# 02_PMIC_POWER.net
KiCad netlist of a schematic drawn in Altium Designer
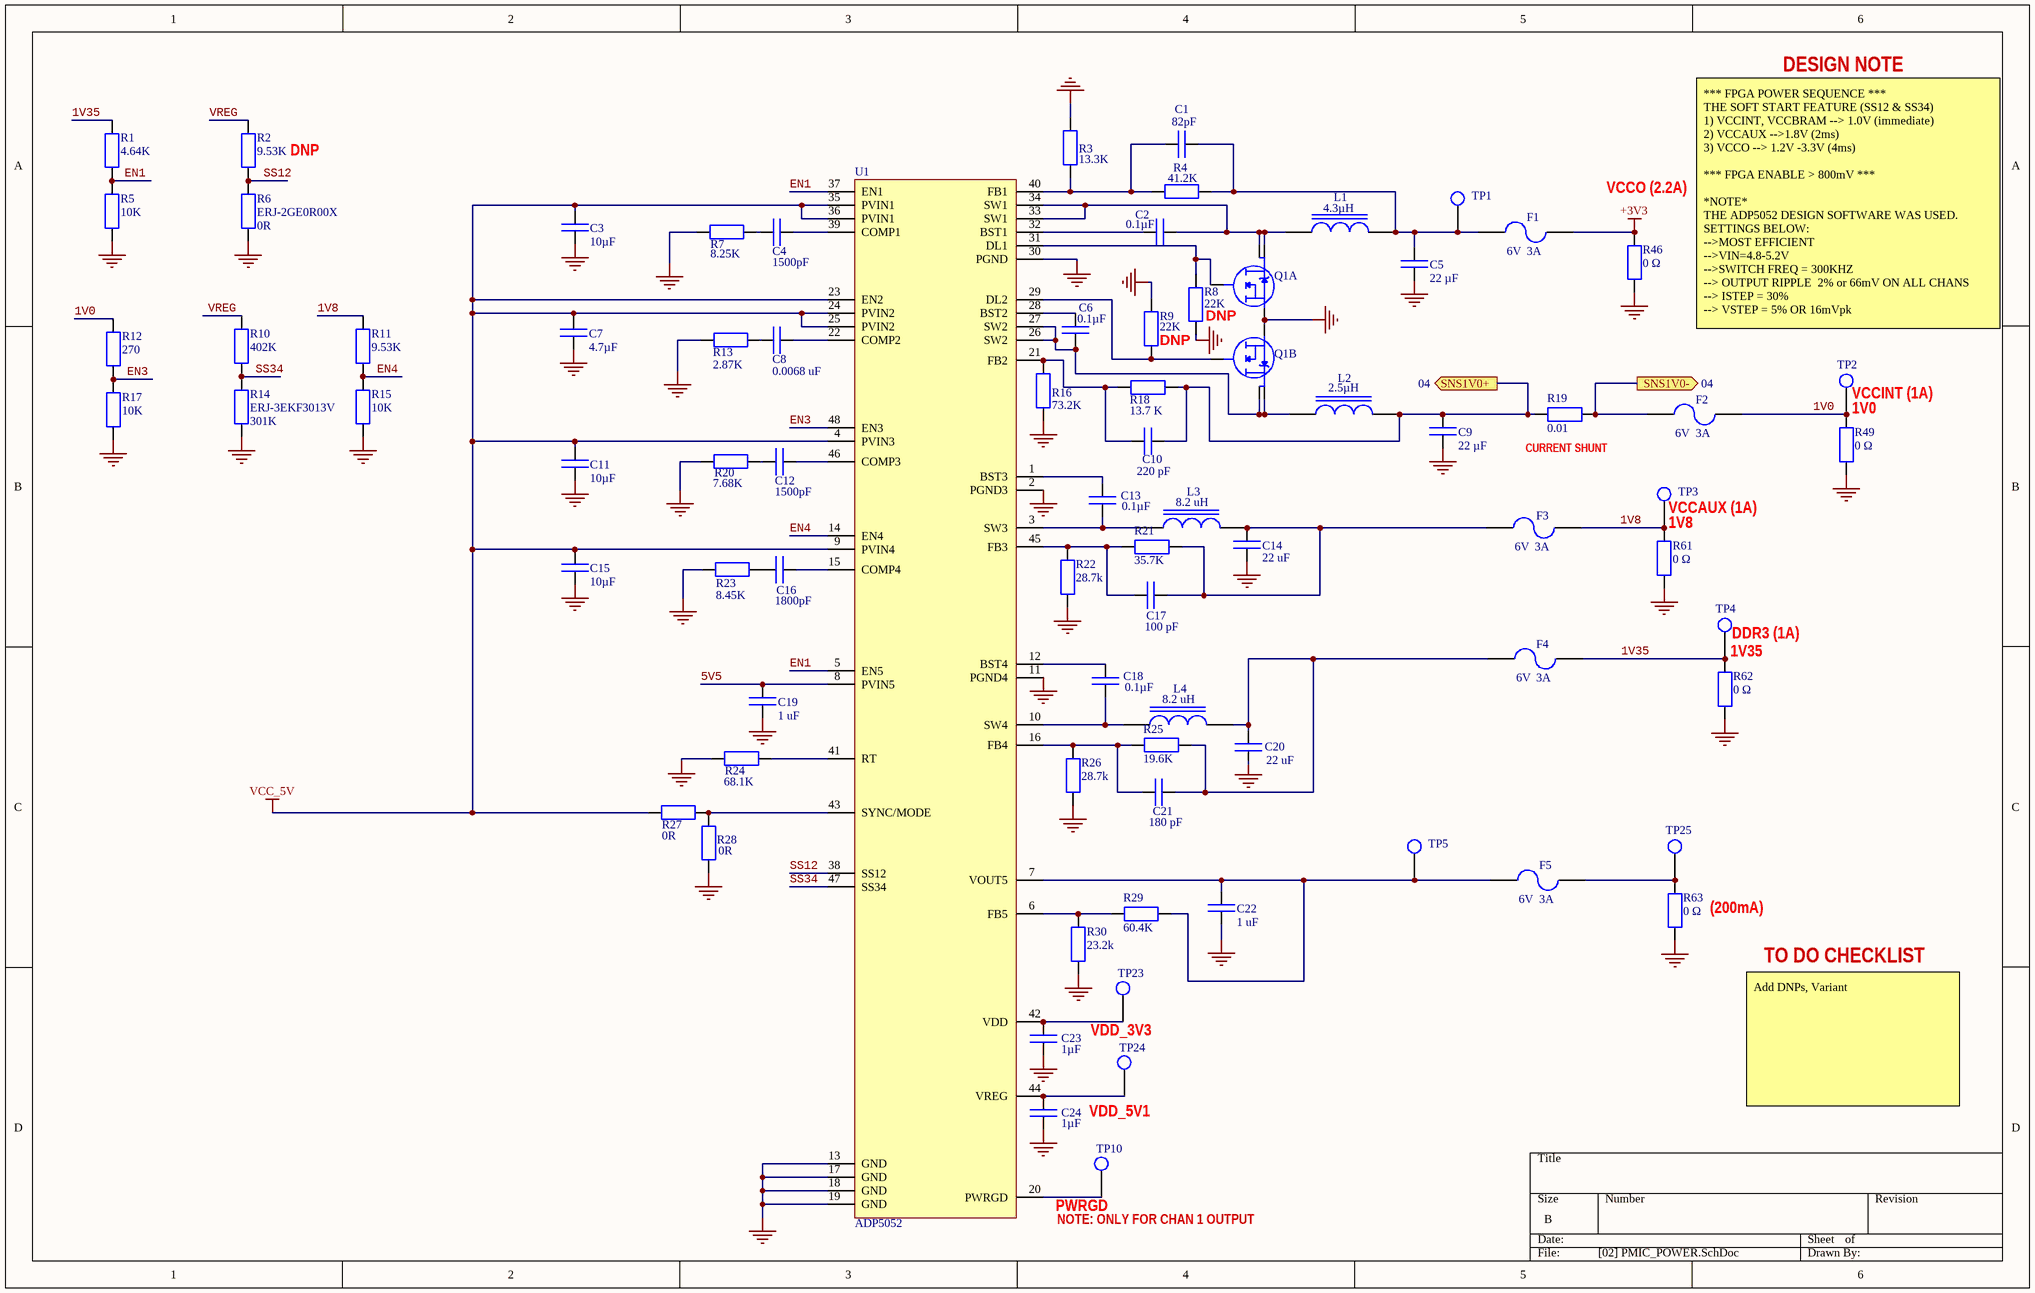
[diagram p0: [02] PMIC_POWER.SchDoc]

(export (version "E")
  (design (tool "Eeschema 10.0.6"))
  (components
    (comp (ref "C1")
      (value "GCM1555C1H820FA16D")
      (footprint "R0402")
      (description "CAP CER 82PF 50V C0G/NP0 0402")
      (fields
        (field (name "MANUFACTURER") "Murata")
        (field (name "CAPACITANCE") "82pF")
        (field (name "TOLERANCE") "±1%")
      )
      (libsource (lib "Honey_Badger") (part "GCM1555C1H820FA16D"))
    )
    (comp (ref "C2")
      (value "CC0402KRX7R6BB104")
      (footprint "R0402")
      (description "0402 0.1 uF 10 V ±10 % Tolerance X7R SMT Multilayer Ceramic Capacitor")
      (fields
        (field (name "MANUFACTURER") "Yageo")
        (field (name "TOLERANCE") "±10%")
        (field (name "CAPACITANCE") "0.1µF")
      )
      (libsource (lib "Honey_Badger") (part "CC0402KRX7R6BB104"))
    )
    (comp (ref "C3")
      (value "C3216X5R1C106M160AA")
      (footprint "C1206")
      (description "CAP CER 10UF 16V X5R 1206")
      (fields
        (field (name "MANUFACTURER") "TDK")
        (field (name "PCN PART NUMBER") "MLCC Part Number Change 30/Nov/2012")
        (field (name "CAPACITANCE") "10µF")
      )
      (libsource (lib "Honey_Badger") (part "C3216X5R1C106M160AA"))
    )
    (comp (ref "C4")
      (value "GCM155R71H152KA37D")
      (footprint "R0402")
      (description "CAP CER 1500PF 50V X7R 0402")
      (fields
        (field (name "MANUFACTURER") "Murata")
        (field (name "TOLERANCE") "±10%")
        (field (name "CAPACITANCE") "1500pF")
      )
      (libsource (lib "Honey_Badger") (part "GCM155R71H152KA37D"))
    )
    (comp (ref "C5")
      (value "12063D226KAT2A")
      (footprint "C1206")
      (description "1206 25 V 22 uF X5R ±10% Tolerance SMT Multilayer Ceramic Capacitor")
      (fields (field (name "MANUFACTURER") "Kyocera AVX") (field (name "CAPACITANCE") "22 µF"))
      (libsource (lib "Honey_Badger") (part "12063D226KAT2A"))
    )
    (comp (ref "C6")
      (value "CC0402KRX7R6BB104")
      (footprint "R0402")
      (description "0402 0.1 uF 10 V ±10 % Tolerance X7R SMT Multilayer Ceramic Capacitor")
      (fields
        (field (name "MANUFACTURER") "Yageo")
        (field (name "TOLERANCE") "±10%")
        (field (name "CAPACITANCE") "0.1µF")
      )
      (libsource (lib "Honey_Badger") (part "CC0402KRX7R6BB104"))
    )
    (comp (ref "C7")
      (value "C2012X5R1C475K060AC")
      (footprint "C0805_1")
      (description "CAP CER 4.7UF 16V X5R 0805")
      (fields
        (field (name "MANUFACTURER") "TDK")
        (field (name "TOLERANCE") "±10%")
        (field (name "CAPACITANCE") "4.7µF")
      )
      (libsource (lib "Honey_Badger") (part "C2012X5R1C475K060AC"))
    )
    (comp (ref "C8")
      (value "GCM155R71H682KA55D")
      (footprint "R0402")
      (description "CAP CER 6800PF 50V X7R 0402")
      (fields
        (field (name "MANUFACTURER") "Murata")
        (field (name "VOLTAGE") "50 Vdc")
        (field (name "CAPACITANCE VALUE") "0.0068 uF")
      )
      (libsource (lib "Honey_Badger") (part "GCM155R71H682KA55D"))
    )
    (comp (ref "C9")
      (value "12063D226KAT2A")
      (footprint "C1206")
      (description "1206 25 V 22 uF X5R ±10% Tolerance SMT Multilayer Ceramic Capacitor")
      (fields (field (name "MANUFACTURER") "Kyocera AVX") (field (name "CAPACITANCE") "22 µF"))
      (libsource (lib "Honey_Badger") (part "12063D226KAT2A"))
    )
    (comp (ref "C10")
      (value "GCM155R71H221KA37D")
      (footprint "R0402")
      (description "CAP CER 220PF 50V X7R 0402")
      (fields
        (field (name "MANUFACTURER") "Murata")
        (field (name "VOLTAGE") "50 Vdc")
        (field (name "CAPACITANCE VALUE") "220 pF")
      )
      (libsource (lib "Honey_Badger") (part "GCM155R71H221KA37D"))
    )
    (comp (ref "C11")
      (value "C3216X5R1C106M160AA")
      (footprint "C1206")
      (description "CAP CER 10UF 16V X5R 1206")
      (fields
        (field (name "MANUFACTURER") "TDK")
        (field (name "PCN PART NUMBER") "MLCC Part Number Change 30/Nov/2012")
        (field (name "CAPACITANCE") "10µF")
      )
      (libsource (lib "Honey_Badger") (part "C3216X5R1C106M160AA"))
    )
    (comp (ref "C12")
      (value "GCM155R71H152KA37D")
      (footprint "R0402")
      (description "CAP CER 1500PF 50V X7R 0402")
      (fields
        (field (name "MANUFACTURER") "Murata")
        (field (name "TOLERANCE") "±10%")
        (field (name "CAPACITANCE") "1500pF")
      )
      (libsource (lib "Honey_Badger") (part "GCM155R71H152KA37D"))
    )
    (comp (ref "C13")
      (value "CC0402KRX7R6BB104")
      (footprint "R0402")
      (description "0402 0.1 uF 10 V ±10 % Tolerance X7R SMT Multilayer Ceramic Capacitor")
      (fields
        (field (name "MANUFACTURER") "Yageo")
        (field (name "TOLERANCE") "±10%")
        (field (name "CAPACITANCE") "0.1µF")
      )
      (libsource (lib "Honey_Badger") (part "CC0402KRX7R6BB104"))
    )
    (comp (ref "C14")
      (value "GRM21BR60J226ME39K")
      (footprint "C0805_1")
      (description "Cap Ceramic 22uF 6.3V X5R 20% SMD 0805 85C Embossed T/R")
      (fields
        (field (name "MANUFACTURER") "Murata")
        (field (name "VOLTAGE") "6.3 Vdc")
        (field (name "CAPACITANCE VALUE") "22 uF")
      )
      (libsource (lib "Honey_Badger") (part "GRM21BR60J226ME39K"))
    )
    (comp (ref "C15")
      (value "C3216X5R1C106M160AA")
      (footprint "C1206")
      (description "CAP CER 10UF 16V X5R 1206")
      (fields
        (field (name "MANUFACTURER") "TDK")
        (field (name "PCN PART NUMBER") "MLCC Part Number Change 30/Nov/2012")
        (field (name "CAPACITANCE") "10µF")
      )
      (libsource (lib "Honey_Badger") (part "C3216X5R1C106M160AA"))
    )
    (comp (ref "C16")
      (value "GRM2165C2A182JA01D")
      (footprint "C0805_1")
      (description "CAP CER 1800PF 100V C0G/NP0 0805")
      (fields
        (field (name "MANUFACTURER") "Murata")
        (field (name "TOLERANCE") "±5%")
        (field (name "CAPACITANCE") "1800pF")
      )
      (libsource (lib "Honey_Badger") (part "GRM2165C2A182JA01D"))
    )
    (comp (ref "C17")
      (value "C0402C101K4GACTU")
      (footprint "R0402")
      (description "CAP CER 100PF 16V C0G/NP0 0402")
      (fields
        (field (name "MANUFACTURER") "KEMET")
        (field (name "TOLERANCE") "10 %")
        (field (name "CAPACITANCE") "100 pF")
      )
      (libsource (lib "Honey_Badger") (part "C0402C101K4GACTU"))
    )
    (comp (ref "C18")
      (value "CC0402KRX7R6BB104")
      (footprint "R0402")
      (description "0402 0.1 uF 10 V ±10 % Tolerance X7R SMT Multilayer Ceramic Capacitor")
      (fields
        (field (name "MANUFACTURER") "Yageo")
        (field (name "TOLERANCE") "±10%")
        (field (name "CAPACITANCE") "0.1µF")
      )
      (libsource (lib "Honey_Badger") (part "CC0402KRX7R6BB104"))
    )
    (comp (ref "C19")
      (value "C0603C105K8RACTU")
      (footprint "C0603_1")
      (description "CAP CER 1UF 10V X7R 0603")
      (fields
        (field (name "MANUFACTURER") "KEMET")
        (field (name "TOLERANCE") "10 %")
        (field (name "CAPACITANCE") "1 uF")
      )
      (libsource (lib "Honey_Badger") (part "C0603C105K8RACTU"))
    )
    (comp (ref "C20")
      (value "GRM21BR60J226ME39K")
      (footprint "C0805_1")
      (description "Cap Ceramic 22uF 6.3V X5R 20% SMD 0805 85C Embossed T/R")
      (fields
        (field (name "MANUFACTURER") "Murata")
        (field (name "VOLTAGE") "6.3 Vdc")
        (field (name "CAPACITANCE VALUE") "22 uF")
      )
      (libsource (lib "Honey_Badger") (part "GRM21BR60J226ME39K"))
    )
    (comp (ref "C21")
      (value "C0402C181K5RACTU")
      (footprint "R0402")
      (description "CAP CER 180PF 50V X7R 0402")
      (fields
        (field (name "MANUFACTURER") "KEMET")
        (field (name "TOLERANCE") "10 %")
        (field (name "CAPACITANCE") "180 pF")
      )
      (libsource (lib "Honey_Badger") (part "C0402C181K5RACTU"))
    )
    (comp (ref "C22")
      (value "C0603C105K8RACTU")
      (footprint "C0603_1")
      (description "CAP CER 1UF 10V X7R 0603")
      (fields
        (field (name "MANUFACTURER") "KEMET")
        (field (name "TOLERANCE") "10 %")
        (field (name "CAPACITANCE") "1 uF")
      )
      (libsource (lib "Honey_Badger") (part "C0603C105K8RACTU"))
    )
    (comp (ref "C23")
      (value "CC0402KRX5R5BB105")
      (description "CAP CER 1UF 6.3V X5R 0402")
      (fields
        (field (name "MANUFACTURER") "Yageo")
        (field (name "CAPACITANCE") "1µF")
        (field (name "TOLERANCE") "±10%")
      )
      (libsource (lib "Honey_Badger") (part "CC0402KRX5R5BB105"))
    )
    (comp (ref "C24")
      (value "CC0402KRX5R5BB105")
      (description "CAP CER 1UF 6.3V X5R 0402")
      (fields
        (field (name "MANUFACTURER") "Yageo")
        (field (name "CAPACITANCE") "1µF")
        (field (name "TOLERANCE") "±10%")
      )
      (libsource (lib "Honey_Badger") (part "CC0402KRX5R5BB105"))
    )
    (comp (ref "F1")
      (value "MF-NSML300-2")
      (footprint "C1206 - PTC")
      (description "PTC FUSE 3A HOLD 6V 1206")
      (fields
        (field (name "MANUFACTURER") "Bourns")
        (field (name "VOLTAGE - MAX") "6V")
        (field (name "CURRENT - HOLD (IH) (MAX)") "3A")
      )
      (libsource (lib "Honey_Badger") (part "MF-NSML300-2"))
    )
    (comp (ref "F2")
      (value "MF-NSML300-2")
      (footprint "C1206 - PTC")
      (description "PTC FUSE 3A HOLD 6V 1206")
      (fields
        (field (name "MANUFACTURER") "Bourns")
        (field (name "VOLTAGE - MAX") "6V")
        (field (name "CURRENT - HOLD (IH) (MAX)") "3A")
      )
      (libsource (lib "Honey_Badger") (part "MF-NSML300-2"))
    )
    (comp (ref "F3")
      (value "MF-NSML300-2")
      (footprint "C1206 - PTC")
      (description "PTC FUSE 3A HOLD 6V 1206")
      (fields
        (field (name "MANUFACTURER") "Bourns")
        (field (name "VOLTAGE - MAX") "6V")
        (field (name "CURRENT - HOLD (IH) (MAX)") "3A")
      )
      (libsource (lib "Honey_Badger") (part "MF-NSML300-2"))
    )
    (comp (ref "F4")
      (value "MF-NSML300-2")
      (footprint "C1206 - PTC")
      (description "PTC FUSE 3A HOLD 6V 1206")
      (fields
        (field (name "MANUFACTURER") "Bourns")
        (field (name "VOLTAGE - MAX") "6V")
        (field (name "CURRENT - HOLD (IH) (MAX)") "3A")
      )
      (libsource (lib "Honey_Badger") (part "MF-NSML300-2"))
    )
    (comp (ref "F5")
      (value "MF-NSML300-2")
      (footprint "C1206 - PTC")
      (description "PTC FUSE 3A HOLD 6V 1206")
      (fields
        (field (name "MANUFACTURER") "Bourns")
        (field (name "VOLTAGE - MAX") "6V")
        (field (name "CURRENT - HOLD (IH) (MAX)") "3A")
      )
      (libsource (lib "Honey_Badger") (part "MF-NSML300-2"))
    )
    (comp (ref "L1")
      (value "7443552430")
      (footprint "14.3uH_10_2mmX10_2mmX4mm")
      (description "FIXED IND 4.3UH 8A 14.1 MOHM SMD")
      (fields
        (field (name "MANUFACTURER") "Wurth Electronics")
        (field (name "INDUCTANCE") "4.3µH")
        (field (name "TOLERANCE") "±20%")
      )
      (libsource (lib "Honey_Badger") (part "7443552430"))
    )
    (comp (ref "L2")
      (value "7447798250")
      (footprint "2.5UH_10_2MMX10_2MM")
      (description "IND 2.5UH 13.7A 4.95 MOHM")
      (fields
        (field (name "MANUFACTURER") "Wurth Electronics")
        (field (name "TOLERANCE") "±30%")
        (field (name "INDUCTANCE") "2.5µH")
      )
      (libsource (lib "Honey_Badger") (part "7447798250"))
    )
    (comp (ref "L3")
      (value "XAL5050-822MEB")
      (footprint "8.2UH_5.28MMX5.28MM")
      (description "Power inductor, shielded, 20% tol, SMT, RoHS, halogen f")
      (fields
        (field (name "MANUFACTURER") "Coilcraft")
        (field (name "TOLERANCE") "20 %")
        (field (name "INDUCTANCE") "8.2 uH")
      )
      (libsource (lib "Honey_Badger") (part "XAL5050-822MEB"))
    )
    (comp (ref "L4")
      (value "XAL5050-822MEB")
      (footprint "8.2UH_5.28MMX5.28MM")
      (description "Power inductor, shielded, 20% tol, SMT, RoHS, halogen f")
      (fields
        (field (name "MANUFACTURER") "Coilcraft")
        (field (name "TOLERANCE") "20 %")
        (field (name "INDUCTANCE") "8.2 uH")
      )
      (libsource (lib "Honey_Badger") (part "XAL5050-822MEB"))
    )
    (comp (ref "Q1")
      (value "IRF8910")
      (footprint "8-SOIC")
      (fields (field (name "MANUFACTURER") "International Rectifier"))
      (libsource (lib "Honey_Badger") (part "IRF8910"))
    )
    (comp (ref "R1")
      (value "ERJ-3EKF4641V")
      (footprint "R0603")
      (description "RES SMD 4.64K OHM 1% 1/10W 0603")
      (fields (field (name "MANUFACTURER") "Panasonic") (field (name "RESISTANCE") "4.64K"))
      (libsource (lib "Super_Hornet") (part "ERJ-3EKF4641V"))
    )
    (comp (ref "R2")
      (value "ERJ-3EKF9531V")
      (footprint "R0603")
      (description "RES SMD 9.53K OHM 1% 1/10W 0603")
      (fields
        (field (name "MANUFACTURER") "Panasonic")
        (field (name "TOLERANCE") "±1%")
        (field (name "RESISTANCE (OHMS)") "9.53K")
      )
      (libsource (lib "Super_Hornet") (part "ERJ-3EKF9531V"))
    )
    (comp (ref "R3")
      (value "CRCW080513K3FKEA")
      (footprint "R0805")
      (description "RES SMD 13.3K OHM 1% 1/8W 0805")
      (fields
        (field (name "MANUFACTURER") "Vishay")
        (field (name "RESISTANCE (OHMS)") "13.3K")
        (field (name "TOLERANCE") "±1%")
      )
      (libsource (lib "Super_Hornet") (part "CRCW080513K3FKEA"))
    )
    (comp (ref "R4")
      (value "CRCW080541K2FKEA")
      (footprint "R0805")
      (description "RES SMD 41.2K OHM 1% 1/8W 0805")
      (fields
        (field (name "MANUFACTURER") "Vishay")
        (field (name "TOLERANCE") "1 %")
        (field (name "RESISTANCE") "41.2K")
      )
      (libsource (lib "Super_Hornet") (part "CRCW080541K2FKEA"))
    )
    (comp (ref "R5")
      (value "ERJ-3EKF1002V")
      (footprint "R0603")
      (description "RES SMD 10K OHM 1% 1/10W 0603")
      (fields (field (name "MANUFACTURER") "Panasonic") (field (name "RESISTANCE") "10K"))
      (libsource (lib "Super_Hornet") (part "ERJ-3EKF1002V"))
    )
    (comp (ref "R6")
      (value "ERJ-2GE0R00X")
      (footprint "R0603")
      (description "RES SMD 0 OHM JUMPER 1/10W 0402")
      (fields
        (field (name "MANUFACTURER") "Panasonic")
        (field (name "TOLERANCE") "Jumper")
        (field (name "RESISTANCE (OHMS)") "0R")
      )
      (libsource (lib "Super_Hornet") (part "ERJ-2GE0R00X"))
    )
    (comp (ref "R7")
      (value "ERJ-6ENF8251V")
      (footprint "R0805")
      (description "RES SMD 8.25K OHM 1% 1/8W 0805")
      (fields (field (name "MANUFACTURER") "Panasonic") (field (name "RESISTANCE") "8.25K"))
      (libsource (lib "Super_Hornet") (part "ERJ-6ENF8251V"))
    )
    (comp (ref "R8")
      (value "CRCW040222K0FKED")
      (footprint "R0402")
      (description "RES SMD 22K OHM 1% 1/16W 0402")
      (fields
        (field (name "MANUFACTURER") "Vishay")
        (field (name "TOLERANCE") "1 %")
        (field (name "RESISTANCE") "22K")
      )
      (libsource (lib "Super_Hornet") (part "CRCW040222K0FKED"))
    )
    (comp (ref "R9")
      (value "CRCW040222K0FKED")
      (footprint "R0402")
      (description "RES SMD 22K OHM 1% 1/16W 0402")
      (fields
        (field (name "MANUFACTURER") "Vishay")
        (field (name "TOLERANCE") "1 %")
        (field (name "RESISTANCE") "22K")
      )
      (libsource (lib "Super_Hornet") (part "CRCW040222K0FKED"))
    )
    (comp (ref "R10")
      (value "ERJ-3EKF4023V")
      (footprint "R0603")
      (description "RES SMD 402K OHM 1% 1/10W 0603")
      (fields
        (field (name "MANUFACTURER") "Panasonic")
        (field (name "TOLERANCE") "±1%")
        (field (name "RESISTANCE (OHMS)") "402K")
      )
      (libsource (lib "Super_Hornet") (part "ERJ-3EKF4023V"))
    )
    (comp (ref "R11")
      (value "ERJ-3EKF9531V")
      (footprint "R0603")
      (description "RES SMD 9.53K OHM 1% 1/10W 0603")
      (fields
        (field (name "MANUFACTURER") "Panasonic")
        (field (name "TOLERANCE") "±1%")
        (field (name "RESISTANCE (OHMS)") "9.53K")
      )
      (libsource (lib "Super_Hornet") (part "ERJ-3EKF9531V"))
    )
    (comp (ref "R12")
      (value "ERJ-3EKF2700V")
      (footprint "R0603")
      (description "RES SMD 270 OHM 1% 1/10W 0603")
      (fields (field (name "MANUFACTURER") "Panasonic") (field (name "RESISTANCE") "270"))
      (libsource (lib "Super_Hornet") (part "ERJ-3EKF2700V"))
    )
    (comp (ref "R13")
      (value "RC0805FR-072K87L")
      (footprint "R0805")
      (description "RES SMD 2.87K OHM 1% 1/8W 0805")
      (fields
        (field (name "MANUFACTURER") "Yageo")
        (field (name "TOLERANCE") "±1%")
        (field (name "RESISTANCE (OHMS)") "2.87K")
      )
      (libsource (lib "Super_Hornet") (part "RC0805FR-072K87L"))
    )
    (comp (ref "R14")
      (value "ERJ-3EKF3013V")
      (footprint "R0603")
      (description "RES SMD 301K OHM 1% 1/10W 0603")
      (fields (field (name "MANUFACTURER") "Panasonic") (field (name "RESISTANCE") "301K"))
      (libsource (lib "Super_Hornet") (part "ERJ-3EKF3013V"))
    )
    (comp (ref "R15")
      (value "ERJ-3EKF1002V")
      (footprint "R0603")
      (description "RES SMD 10K OHM 1% 1/10W 0603")
      (fields (field (name "MANUFACTURER") "Panasonic") (field (name "RESISTANCE") "10K"))
      (libsource (lib "Super_Hornet") (part "ERJ-3EKF1002V"))
    )
    (comp (ref "R16")
      (value "ERJ-2RKF7322X")
      (footprint "R0402")
      (description "RES SMD 73.2K OHM 1% 1/10W 0402")
      (fields (field (name "MANUFACTURER") "Panasonic") (field (name "RESISTANCE") "73.2K"))
      (libsource (lib "Super_Hornet") (part "ERJ-2RKF7322X"))
    )
    (comp (ref "R17")
      (value "ERJ-3EKF1002V")
      (footprint "R0603")
      (description "RES SMD 10K OHM 1% 1/10W 0603")
      (fields (field (name "MANUFACTURER") "Panasonic") (field (name "RESISTANCE") "10K"))
      (libsource (lib "Super_Hornet") (part "ERJ-3EKF1002V"))
    )
    (comp (ref "R18")
      (value "ERJ-2RKF1372X")
      (footprint "R0402")
      (description "RES SMD 13.7K OHM 1% 1/10W 0402")
      (fields
        (field (name "MANUFACTURER") "Panasonic")
        (field (name "TOLERANCE") "1 %")
        (field (name "RESISTANCE") "13.7 K")
      )
      (libsource (lib "Super_Hornet") (part "ERJ-2RKF1372X"))
    )
    (comp (ref "R19")
      (value "ERJ-3LWFR010V")
      (footprint "R0603")
      (description "RES SMD 0.01 OHM 1% 1/4W 0603")
      (fields
        (field (name "MANUFACTURER") "Panasonic")
        (field (name "TOLERANCE") "±1%")
        (field (name "RESISTANCE (OHMS)") "0.01")
      )
      (libsource (lib "Super_Hornet") (part "ERJ-3LWFR010V"))
    )
    (comp (ref "R20")
      (value "ERJ-6ENF7681V")
      (footprint "R0805")
      (description "RES SMD 7.68K OHM 1% 1/8W 0805")
      (fields
        (field (name "MANUFACTURER") "Panasonic")
        (field (name "TOLERANCE") "±1%")
        (field (name "RESISTANCE (OHMS)") "7.68K")
      )
      (libsource (lib "Super_Hornet") (part "ERJ-6ENF7681V"))
    )
    (comp (ref "R21")
      (value "ERJ-2RKF3572X")
      (footprint "R0402")
      (description "RES SMD 35.7K OHM 1% 1/10W 0402")
      (fields (field (name "MANUFACTURER") "Panasonic") (field (name "RESISTANCE") "35.7K"))
      (libsource (lib "Super_Hornet") (part "ERJ-2RKF3572X"))
    )
    (comp (ref "R22")
      (value "CRCW040228K7FKED")
      (footprint "R0402")
      (description "RES SMD 28.7K OHM 1% 1/16W 0402")
      (fields
        (field (name "MANUFACTURER") "Vishay")
        (field (name "TOLERANCE") "±1%")
        (field (name "RESISTANCE (OHMS)") "28.7k")
      )
      (libsource (lib "Super_Hornet") (part "CRCW040228K7FKED"))
    )
    (comp (ref "R23")
      (value "ERJ-6ENF8451V")
      (footprint "R0805")
      (description "RES SMD 8.45K OHM 1% 1/8W 0805")
      (fields (field (name "MANUFACTURER") "Panasonic") (field (name "RESISTANCE") "8.45K"))
      (libsource (lib "Super_Hornet") (part "ERJ-6ENF8451V"))
    )
    (comp (ref "R24")
      (value "ERJ-2RKF6812X")
      (footprint "R0402")
      (description "RES SMD 68.1K OHM 1% 1/10W 0402")
      (fields (field (name "MANUFACTURER") "Panasonic") (field (name "RESISTANCE") "68.1K"))
      (libsource (lib "Super_Hornet") (part "ERJ-2RKF6812X"))
    )
    (comp (ref "R25")
      (value "ERJ-2RKF1962X")
      (footprint "R0402")
      (description "RES SMD 19.6K OHM 1% 1/10W 0402")
      (fields (field (name "MANUFACTURER") "Panasonic") (field (name "RESISTANCE") "19.6K"))
      (libsource (lib "Super_Hornet") (part "ERJ-2RKF1962X"))
    )
    (comp (ref "R26")
      (value "CRCW040228K7FKED")
      (footprint "R0402")
      (description "RES SMD 28.7K OHM 1% 1/16W 0402")
      (fields
        (field (name "MANUFACTURER") "Vishay")
        (field (name "TOLERANCE") "±1%")
        (field (name "RESISTANCE (OHMS)") "28.7k")
      )
      (libsource (lib "Super_Hornet") (part "CRCW040228K7FKED"))
    )
    (comp (ref "R27")
      (value "ERJ-2GE0R00X")
      (footprint "R0603")
      (description "RES SMD 0 OHM JUMPER 1/10W 0402")
      (fields
        (field (name "MANUFACTURER") "Panasonic")
        (field (name "TOLERANCE") "Jumper")
        (field (name "RESISTANCE (OHMS)") "0R")
      )
      (libsource (lib "Super_Hornet") (part "ERJ-2GE0R00X"))
    )
    (comp (ref "R28")
      (value "ERJ-2GE0R00X")
      (footprint "R0603")
      (description "RES SMD 0 OHM JUMPER 1/10W 0402")
      (fields
        (field (name "MANUFACTURER") "Panasonic")
        (field (name "TOLERANCE") "Jumper")
        (field (name "RESISTANCE (OHMS)") "0R")
      )
      (libsource (lib "Super_Hornet") (part "ERJ-2GE0R00X"))
    )
    (comp (ref "R29")
      (value "ERJ-2RKF6042X")
      (footprint "R0402")
      (description "RES SMD 60.4K OHM 1% 1/10W 0402")
      (fields (field (name "MANUFACTURER") "Panasonic") (field (name "RESISTANCE") "60.4K"))
      (libsource (lib "Super_Hornet") (part "ERJ-2RKF6042X"))
    )
    (comp (ref "R30")
      (value "ERJ-2RKF2322X")
      (footprint "R0402")
      (description "RES SMD 23.2K OHM 1% 1/10W 0402")
      (fields
        (field (name "MANUFACTURER") "Panasonic")
        (field (name "TOLERANCE") "±1%")
        (field (name "RESISTANCE (OHMS)") "23.2k")
      )
      (libsource (lib "Super_Hornet") (part "ERJ-2RKF2322X"))
    )
    (comp (ref "R46")
      (value "ERJ-6GEY0R00V")
      (footprint "R0805")
      (description "RES SMD 0 OHM JUMPER 1/8W 0805")
      (fields (field (name "MANUFACTURER") "Panasonic") (field (name "RESISTANCE") "0 Ω"))
      (libsource (lib "Super_Hornet") (part "ERJ-6GEY0R00V"))
    )
    (comp (ref "R49")
      (value "ERJ-6GEY0R00V")
      (footprint "R0805")
      (description "RES SMD 0 OHM JUMPER 1/8W 0805")
      (fields (field (name "MANUFACTURER") "Panasonic") (field (name "RESISTANCE") "0 Ω"))
      (libsource (lib "Super_Hornet") (part "ERJ-6GEY0R00V"))
    )
    (comp (ref "R61")
      (value "ERJ-6GEY0R00V")
      (footprint "R0805")
      (description "RES SMD 0 OHM JUMPER 1/8W 0805")
      (fields (field (name "MANUFACTURER") "Panasonic") (field (name "RESISTANCE") "0 Ω"))
      (libsource (lib "Super_Hornet") (part "ERJ-6GEY0R00V"))
    )
    (comp (ref "R62")
      (value "ERJ-6GEY0R00V")
      (footprint "R0805")
      (description "RES SMD 0 OHM JUMPER 1/8W 0805")
      (fields (field (name "MANUFACTURER") "Panasonic") (field (name "RESISTANCE") "0 Ω"))
      (libsource (lib "Super_Hornet") (part "ERJ-6GEY0R00V"))
    )
    (comp (ref "R63")
      (value "ERJ-6GEY0R00V")
      (footprint "R0805")
      (description "RES SMD 0 OHM JUMPER 1/8W 0805")
      (fields (field (name "MANUFACTURER") "Panasonic") (field (name "RESISTANCE") "0 Ω"))
      (libsource (lib "Super_Hornet") (part "ERJ-6GEY0R00V"))
    )
    (comp (ref "TP1")
      (value "5017")
      (footprint "TEST_POINT")
      (description "PCB MINI TEST POINT")
      (fields (field (name "MANUFACTURER") "Keystone Electronics"))
      (libsource (lib "Honey_Badger") (part "5017"))
    )
    (comp (ref "TP2")
      (value "5017")
      (footprint "TEST_POINT")
      (description "PCB MINI TEST POINT")
      (fields (field (name "MANUFACTURER") "Keystone Electronics"))
      (libsource (lib "Honey_Badger") (part "5017"))
    )
    (comp (ref "TP3")
      (value "5017")
      (footprint "TEST_POINT")
      (description "PCB MINI TEST POINT")
      (fields (field (name "MANUFACTURER") "Keystone Electronics"))
      (libsource (lib "Honey_Badger") (part "5017"))
    )
    (comp (ref "TP4")
      (value "5017")
      (footprint "TEST_POINT")
      (description "PCB MINI TEST POINT")
      (fields (field (name "MANUFACTURER") "Keystone Electronics"))
      (libsource (lib "Honey_Badger") (part "5017"))
    )
    (comp (ref "TP5")
      (value "5017")
      (footprint "TEST_POINT")
      (description "PCB MINI TEST POINT")
      (fields (field (name "MANUFACTURER") "Keystone Electronics"))
      (libsource (lib "Honey_Badger") (part "5017"))
    )
    (comp (ref "TP10")
      (value "5017")
      (footprint "TEST_POINT")
      (description "PCB MINI TEST POINT")
      (fields (field (name "MANUFACTURER") "Keystone Electronics"))
      (libsource (lib "Super_Hornet") (part "5017"))
    )
    (comp (ref "TP23")
      (value "5017")
      (footprint "TEST_POINT")
      (description "PCB MINI TEST POINT")
      (fields (field (name "MANUFACTURER") "Keystone Electronics"))
      (libsource (lib "Super_Hornet") (part "5017"))
    )
    (comp (ref "TP24")
      (value "5017")
      (footprint "TEST_POINT")
      (description "PCB MINI TEST POINT")
      (fields (field (name "MANUFACTURER") "Keystone Electronics"))
      (libsource (lib "Super_Hornet") (part "5017"))
    )
    (comp (ref "TP25")
      (value "5017")
      (footprint "TEST_POINT")
      (description "PCB MINI TEST POINT")
      (fields (field (name "MANUFACTURER") "Keystone Electronics"))
      (libsource (lib "Honey_Badger") (part "5017"))
    )
    (comp (ref "U1")
      (value "ADP5052")
      (footprint "48-LFSCP")
      (description "PMIC 4BUCK_1LDO")
      (fields
        (field (name "MANUFACTURER") "Analog Devices")
        (field (name "MANUFACTURER PART NUMBER") "ADP5052ACPZ-R7")
      )
      (libsource (lib "Honey_Badger") (part "ADP5052ACPZ-R7"))
    )
  )
  (nets
    (net (code "1") (name "+3V3") (class "Default")
      (node (ref "F1") (pin "2") (pinfunction "2_2") (pintype "passive"))
      (node (ref "R46") (pin "1") (pinfunction "1_1") (pintype "passive"))
    )
    (net (code "2") (name "/1V0") (class "Default")
      (node (ref "F2") (pin "2") (pinfunction "2_2") (pintype "passive"))
      (node (ref "R12") (pin "2") (pinfunction "2_2") (pintype "passive"))
      (node (ref "R49") (pin "1") (pinfunction "1_1") (pintype "passive"))
      (node (ref "TP2") (pin "1") (pinfunction "1_1") (pintype "passive"))
    )
    (net (code "3") (name "/1V8") (class "Default")
      (node (ref "F3") (pin "2") (pinfunction "2_2") (pintype "passive"))
      (node (ref "R11") (pin "2") (pinfunction "2_2") (pintype "passive"))
      (node (ref "R61") (pin "1") (pinfunction "1_1") (pintype "passive"))
      (node (ref "TP3") (pin "1") (pinfunction "1_1") (pintype "passive"))
    )
    (net (code "4") (name "/1V35") (class "Default")
      (node (ref "F4") (pin "2") (pinfunction "2_2") (pintype "passive"))
      (node (ref "R1") (pin "2") (pinfunction "2_2") (pintype "passive"))
      (node (ref "R62") (pin "1") (pinfunction "1_1") (pintype "passive"))
      (node (ref "TP4") (pin "1") (pinfunction "1_1") (pintype "passive"))
    )
    (net (code "5") (name "/5V5") (class "Default")
      (node (ref "C19") (pin "2") (pinfunction "2_2") (pintype "passive"))
      (node (ref "U1") (pin "8") (pinfunction "PVIN5_8") (pintype "passive"))
    )
    (net (code "6") (name "/EN1") (class "Default")
      (node (ref "R1") (pin "1") (pinfunction "1_1") (pintype "passive"))
      (node (ref "R5") (pin "2") (pinfunction "2_2") (pintype "passive"))
      (node (ref "U1") (pin "37") (pinfunction "EN1_37") (pintype "passive"))
      (node (ref "U1") (pin "5") (pinfunction "EN5_5") (pintype "passive"))
    )
    (net (code "7") (name "/EN3") (class "Default")
      (node (ref "R12") (pin "1") (pinfunction "1_1") (pintype "passive"))
      (node (ref "R17") (pin "2") (pinfunction "2_2") (pintype "passive"))
      (node (ref "U1") (pin "48") (pinfunction "EN3_48") (pintype "passive"))
    )
    (net (code "8") (name "/EN4") (class "Default")
      (node (ref "R11") (pin "1") (pinfunction "1_1") (pintype "passive"))
      (node (ref "R15") (pin "2") (pinfunction "2_2") (pintype "passive"))
      (node (ref "U1") (pin "14") (pinfunction "EN4_14") (pintype "passive"))
    )
    (net (code "9") (name "/SNS1V0+") (class "Default")
      (node (ref "C10") (pin "1") (pinfunction "1_1") (pintype "passive"))
      (node (ref "C9") (pin "2") (pinfunction "2_2") (pintype "passive"))
      (node (ref "L2") (pin "2") (pinfunction "2_2") (pintype "passive"))
      (node (ref "R18") (pin "1") (pinfunction "1_1") (pintype "passive"))
      (node (ref "R19") (pin "1") (pinfunction "1_1") (pintype "passive"))
    )
    (net (code "10") (name "/SNS1V0-") (class "Default")
      (node (ref "F2") (pin "1") (pinfunction "1_1") (pintype "passive"))
      (node (ref "R19") (pin "2") (pinfunction "2_2") (pintype "passive"))
    )
    (net (code "11") (name "/SS12") (class "Default")
      (node (ref "R2") (pin "1") (pinfunction "1_1") (pintype "passive"))
      (node (ref "R6") (pin "2") (pinfunction "2_2") (pintype "passive"))
      (node (ref "U1") (pin "38") (pinfunction "SS12_38") (pintype "passive"))
    )
    (net (code "12") (name "/SS34") (class "Default")
      (node (ref "R10") (pin "1") (pinfunction "1_1") (pintype "passive"))
      (node (ref "R14") (pin "2") (pinfunction "2_2") (pintype "passive"))
      (node (ref "U1") (pin "47") (pinfunction "SS34_47") (pintype "passive"))
    )
    (net (code "13") (name "/VREG") (class "Default")
      (node (ref "R10") (pin "2") (pinfunction "2_2") (pintype "passive"))
      (node (ref "R2") (pin "2") (pinfunction "2_2") (pintype "passive"))
    )
    (net (code "14") (name "GND") (class "Default")
      (node (ref "C11") (pin "1") (pinfunction "1_1") (pintype "passive"))
      (node (ref "C14") (pin "1") (pinfunction "1_1") (pintype "passive"))
      (node (ref "C15") (pin "1") (pinfunction "1_1") (pintype "passive"))
      (node (ref "C19") (pin "1") (pinfunction "1_1") (pintype "passive"))
      (node (ref "C20") (pin "1") (pinfunction "1_1") (pintype "passive"))
      (node (ref "C22") (pin "1") (pinfunction "1_1") (pintype "passive"))
      (node (ref "C23") (pin "1") (pinfunction "1_1") (pintype "passive"))
      (node (ref "C24") (pin "1") (pinfunction "1_1") (pintype "passive"))
      (node (ref "C3") (pin "1") (pinfunction "1_1") (pintype "passive"))
      (node (ref "C5") (pin "1") (pinfunction "1_1") (pintype "passive"))
      (node (ref "C7") (pin "1") (pinfunction "1_1") (pintype "passive"))
      (node (ref "C9") (pin "1") (pinfunction "1_1") (pintype "passive"))
      (node (ref "Q1") (pin "1") (pinfunction "S1_1") (pintype "passive"))
      (node (ref "Q1") (pin "3") (pinfunction "S2_3") (pintype "passive"))
      (node (ref "R13") (pin "1") (pinfunction "1_1") (pintype "passive"))
      (node (ref "R14") (pin "1") (pinfunction "1_1") (pintype "passive"))
      (node (ref "R15") (pin "1") (pinfunction "1_1") (pintype "passive"))
      (node (ref "R16") (pin "1") (pinfunction "1_1") (pintype "passive"))
      (node (ref "R17") (pin "1") (pinfunction "1_1") (pintype "passive"))
      (node (ref "R20") (pin "1") (pinfunction "1_1") (pintype "passive"))
      (node (ref "R22") (pin "1") (pinfunction "1_1") (pintype "passive"))
      (node (ref "R23") (pin "1") (pinfunction "1_1") (pintype "passive"))
      (node (ref "R24") (pin "1") (pinfunction "1_1") (pintype "passive"))
      (node (ref "R26") (pin "1") (pinfunction "1_1") (pintype "passive"))
      (node (ref "R28") (pin "2") (pinfunction "2_2") (pintype "passive"))
      (node (ref "R3") (pin "2") (pinfunction "2_2") (pintype "passive"))
      (node (ref "R30") (pin "1") (pinfunction "1_1") (pintype "passive"))
      (node (ref "R46") (pin "2") (pinfunction "2_2") (pintype "passive"))
      (node (ref "R49") (pin "2") (pinfunction "2_2") (pintype "passive"))
      (node (ref "R5") (pin "1") (pinfunction "1_1") (pintype "passive"))
      (node (ref "R6") (pin "1") (pinfunction "1_1") (pintype "passive"))
      (node (ref "R61") (pin "2") (pinfunction "2_2") (pintype "passive"))
      (node (ref "R62") (pin "2") (pinfunction "2_2") (pintype "passive"))
      (node (ref "R63") (pin "2") (pinfunction "2_2") (pintype "passive"))
      (node (ref "R7") (pin "1") (pinfunction "1_1") (pintype "passive"))
      (node (ref "R8") (pin "1") (pinfunction "1_1") (pintype "passive"))
      (node (ref "R9") (pin "2") (pinfunction "2_2") (pintype "passive"))
      (node (ref "U1") (pin "11") (pinfunction "PGND4_11") (pintype "passive"))
      (node (ref "U1") (pin "13") (pinfunction "GND_13") (pintype "passive"))
      (node (ref "U1") (pin "17") (pinfunction "GND_17") (pintype "passive"))
      (node (ref "U1") (pin "18") (pinfunction "GND_18") (pintype "passive"))
      (node (ref "U1") (pin "19") (pinfunction "GND_19") (pintype "passive"))
      (node (ref "U1") (pin "2") (pinfunction "PGND3_2") (pintype "passive"))
      (node (ref "U1") (pin "30") (pinfunction "PGND_30") (pintype "passive"))
    )
    (net (code "15") (name "Net-(C1-Pad1)") (class "Default")
      (node (ref "C1") (pin "1") (pinfunction "1_1") (pintype "passive"))
      (node (ref "C5") (pin "2") (pinfunction "2_2") (pintype "passive"))
      (node (ref "F1") (pin "1") (pinfunction "1_1") (pintype "passive"))
      (node (ref "L1") (pin "2") (pinfunction "2_2") (pintype "passive"))
      (node (ref "R4") (pin "2") (pinfunction "2_2") (pintype "passive"))
      (node (ref "TP1") (pin "1") (pinfunction "1_1") (pintype "passive"))
    )
    (net (code "16") (name "Net-(C2-Pad1)") (class "Default")
      (node (ref "C2") (pin "1") (pinfunction "1_1") (pintype "passive"))
      (node (ref "L1") (pin "1") (pinfunction "1_1") (pintype "passive"))
      (node (ref "Q1") (pin "7") (pinfunction "D1_7") (pintype "passive"))
      (node (ref "Q1") (pin "8") (pinfunction "D1_8") (pintype "passive"))
      (node (ref "U1") (pin "33") (pinfunction "SW1_33") (pintype "passive"))
      (node (ref "U1") (pin "34") (pinfunction "SW1_34") (pintype "passive"))
    )
    (net (code "17") (name "Net-(C4-Pad2)") (class "Default")
      (node (ref "C4") (pin "2") (pinfunction "2_2") (pintype "passive"))
      (node (ref "R7") (pin "2") (pinfunction "2_2") (pintype "passive"))
    )
    (net (code "18") (name "Net-(C6-Pad2)") (class "Default")
      (node (ref "C6") (pin "2") (pinfunction "2_2") (pintype "passive"))
      (node (ref "L2") (pin "1") (pinfunction "1_1") (pintype "passive"))
      (node (ref "Q1") (pin "5") (pinfunction "D2_5") (pintype "passive"))
      (node (ref "Q1") (pin "6") (pinfunction "D2_6") (pintype "passive"))
      (node (ref "U1") (pin "26") (pinfunction "SW2_26") (pintype "passive"))
      (node (ref "U1") (pin "27") (pinfunction "SW2_27") (pintype "passive"))
    )
    (net (code "19") (name "Net-(C8-Pad2)") (class "Default")
      (node (ref "C8") (pin "2") (pinfunction "2_2") (pintype "passive"))
      (node (ref "R13") (pin "2") (pinfunction "2_2") (pintype "passive"))
    )
    (net (code "20") (name "Net-(C12-Pad2)") (class "Default")
      (node (ref "C12") (pin "2") (pinfunction "2_2") (pintype "passive"))
      (node (ref "R20") (pin "2") (pinfunction "2_2") (pintype "passive"))
    )
    (net (code "21") (name "Net-(C14-Pad2)") (class "Default")
      (node (ref "C14") (pin "2") (pinfunction "2_2") (pintype "passive"))
      (node (ref "C17") (pin "1") (pinfunction "1_1") (pintype "passive"))
      (node (ref "F3") (pin "1") (pinfunction "1_1") (pintype "passive"))
      (node (ref "L3") (pin "2") (pinfunction "2_2") (pintype "passive"))
      (node (ref "R21") (pin "2") (pinfunction "2_2") (pintype "passive"))
    )
    (net (code "22") (name "Net-(C16-Pad2)") (class "Default")
      (node (ref "C16") (pin "2") (pinfunction "2_2") (pintype "passive"))
      (node (ref "R23") (pin "2") (pinfunction "2_2") (pintype "passive"))
    )
    (net (code "23") (name "Net-(C20-Pad2)") (class "Default")
      (node (ref "C20") (pin "2") (pinfunction "2_2") (pintype "passive"))
      (node (ref "C21") (pin "1") (pinfunction "1_1") (pintype "passive"))
      (node (ref "F4") (pin "1") (pinfunction "1_1") (pintype "passive"))
      (node (ref "L4") (pin "2") (pinfunction "2_2") (pintype "passive"))
      (node (ref "R25") (pin "2") (pinfunction "2_2") (pintype "passive"))
    )
    (net (code "24") (name "Net-(F5-Pad2)") (class "Default")
      (node (ref "F5") (pin "2") (pinfunction "2_2") (pintype "passive"))
      (node (ref "R63") (pin "1") (pinfunction "1_1") (pintype "passive"))
      (node (ref "TP25") (pin "1") (pinfunction "1_1") (pintype "passive"))
    )
    (net (code "25") (name "Net-(Q1A-G1)") (class "Default")
      (node (ref "Q1") (pin "2") (pinfunction "G1_2") (pintype "passive"))
      (node (ref "R8") (pin "2") (pinfunction "2_2") (pintype "passive"))
      (node (ref "U1") (pin "31") (pinfunction "DL1_31") (pintype "passive"))
    )
    (net (code "26") (name "Net-(Q1B-G2)") (class "Default")
      (node (ref "Q1") (pin "4") (pinfunction "G2_4") (pintype "passive"))
      (node (ref "R9") (pin "1") (pinfunction "1_1") (pintype "passive"))
      (node (ref "U1") (pin "29") (pinfunction "DL2_29") (pintype "passive"))
    )
    (net (code "27") (name "Net-(U1-BST1)") (class "Default")
      (node (ref "C2") (pin "2") (pinfunction "2_2") (pintype "passive"))
      (node (ref "U1") (pin "32") (pinfunction "BST1_32") (pintype "passive"))
    )
    (net (code "28") (name "Net-(U1-BST2)") (class "Default")
      (node (ref "C6") (pin "1") (pinfunction "1_1") (pintype "passive"))
      (node (ref "U1") (pin "28") (pinfunction "BST2_28") (pintype "passive"))
    )
    (net (code "29") (name "Net-(U1-BST3)") (class "Default")
      (node (ref "C13") (pin "1") (pinfunction "1_1") (pintype "passive"))
      (node (ref "U1") (pin "1") (pinfunction "BST3_1") (pintype "passive"))
    )
    (net (code "30") (name "Net-(U1-BST4)") (class "Default")
      (node (ref "C18") (pin "1") (pinfunction "1_1") (pintype "passive"))
      (node (ref "U1") (pin "12") (pinfunction "BST4_12") (pintype "passive"))
    )
    (net (code "31") (name "Net-(U1-COMP1)") (class "Default")
      (node (ref "C4") (pin "1") (pinfunction "1_1") (pintype "passive"))
      (node (ref "U1") (pin "39") (pinfunction "COMP1_39") (pintype "passive"))
    )
    (net (code "32") (name "Net-(U1-COMP2)") (class "Default")
      (node (ref "C8") (pin "1") (pinfunction "1_1") (pintype "passive"))
      (node (ref "U1") (pin "22") (pinfunction "COMP2_22") (pintype "passive"))
    )
    (net (code "33") (name "Net-(U1-COMP3)") (class "Default")
      (node (ref "C12") (pin "1") (pinfunction "1_1") (pintype "passive"))
      (node (ref "U1") (pin "46") (pinfunction "COMP3_46") (pintype "passive"))
    )
    (net (code "34") (name "Net-(U1-COMP4)") (class "Default")
      (node (ref "C16") (pin "1") (pinfunction "1_1") (pintype "passive"))
      (node (ref "U1") (pin "15") (pinfunction "COMP4_15") (pintype "passive"))
    )
    (net (code "35") (name "Net-(U1-FB1)") (class "Default")
      (node (ref "C1") (pin "2") (pinfunction "2_2") (pintype "passive"))
      (node (ref "R3") (pin "1") (pinfunction "1_1") (pintype "passive"))
      (node (ref "R4") (pin "1") (pinfunction "1_1") (pintype "passive"))
      (node (ref "U1") (pin "40") (pinfunction "FB1_40") (pintype "passive"))
    )
    (net (code "36") (name "Net-(U1-FB2)") (class "Default")
      (node (ref "C10") (pin "2") (pinfunction "2_2") (pintype "passive"))
      (node (ref "R16") (pin "2") (pinfunction "2_2") (pintype "passive"))
      (node (ref "R18") (pin "2") (pinfunction "2_2") (pintype "passive"))
      (node (ref "U1") (pin "21") (pinfunction "FB2_21") (pintype "passive"))
    )
    (net (code "37") (name "Net-(U1-FB3)") (class "Default")
      (node (ref "C17") (pin "2") (pinfunction "2_2") (pintype "passive"))
      (node (ref "R21") (pin "1") (pinfunction "1_1") (pintype "passive"))
      (node (ref "R22") (pin "2") (pinfunction "2_2") (pintype "passive"))
      (node (ref "U1") (pin "45") (pinfunction "FB3_45") (pintype "passive"))
    )
    (net (code "38") (name "Net-(U1-FB4)") (class "Default")
      (node (ref "C21") (pin "2") (pinfunction "2_2") (pintype "passive"))
      (node (ref "R25") (pin "1") (pinfunction "1_1") (pintype "passive"))
      (node (ref "R26") (pin "2") (pinfunction "2_2") (pintype "passive"))
      (node (ref "U1") (pin "16") (pinfunction "FB4_16") (pintype "passive"))
    )
    (net (code "39") (name "Net-(U1-FB5)") (class "Default")
      (node (ref "R29") (pin "1") (pinfunction "1_1") (pintype "passive"))
      (node (ref "R30") (pin "2") (pinfunction "2_2") (pintype "passive"))
      (node (ref "U1") (pin "6") (pinfunction "FB5_6") (pintype "passive"))
    )
    (net (code "40") (name "Net-(U1-PWRGD)") (class "Default")
      (node (ref "TP10") (pin "1") (pinfunction "1_1") (pintype "passive"))
      (node (ref "U1") (pin "20") (pinfunction "PWRGD_20") (pintype "passive"))
    )
    (net (code "41") (name "Net-(U1-RT)") (class "Default")
      (node (ref "R24") (pin "2") (pinfunction "2_2") (pintype "passive"))
      (node (ref "U1") (pin "41") (pinfunction "RT_41") (pintype "passive"))
    )
    (net (code "42") (name "Net-(U1-SW3)") (class "Default")
      (node (ref "C13") (pin "2") (pinfunction "2_2") (pintype "passive"))
      (node (ref "L3") (pin "1") (pinfunction "1_1") (pintype "passive"))
      (node (ref "U1") (pin "3") (pinfunction "SW3_3") (pintype "passive"))
    )
    (net (code "43") (name "Net-(U1-SW4)") (class "Default")
      (node (ref "C18") (pin "2") (pinfunction "2_2") (pintype "passive"))
      (node (ref "L4") (pin "1") (pinfunction "1_1") (pintype "passive"))
      (node (ref "U1") (pin "10") (pinfunction "SW4_10") (pintype "passive"))
    )
    (net (code "44") (name "Net-(U1-SYNC{slash}MODE)") (class "Default")
      (node (ref "R27") (pin "1") (pinfunction "1_1") (pintype "passive"))
      (node (ref "R28") (pin "1") (pinfunction "1_1") (pintype "passive"))
      (node (ref "U1") (pin "43") (pinfunction "SYNC/MODE_43") (pintype "passive"))
    )
    (net (code "45") (name "Net-(U1-VDD)") (class "Default")
      (node (ref "C23") (pin "2") (pinfunction "2_2") (pintype "passive"))
      (node (ref "TP23") (pin "1") (pinfunction "1_1") (pintype "passive"))
      (node (ref "U1") (pin "42") (pinfunction "VDD_42") (pintype "passive"))
    )
    (net (code "46") (name "Net-(U1-VOUT5)") (class "Default")
      (node (ref "C22") (pin "2") (pinfunction "2_2") (pintype "passive"))
      (node (ref "F5") (pin "1") (pinfunction "1_1") (pintype "passive"))
      (node (ref "R29") (pin "2") (pinfunction "2_2") (pintype "passive"))
      (node (ref "TP5") (pin "1") (pinfunction "1_1") (pintype "passive"))
      (node (ref "U1") (pin "7") (pinfunction "VOUT5_7") (pintype "passive"))
    )
    (net (code "47") (name "Net-(U1-VREG)") (class "Default")
      (node (ref "C24") (pin "2") (pinfunction "2_2") (pintype "passive"))
      (node (ref "TP24") (pin "1") (pinfunction "1_1") (pintype "passive"))
      (node (ref "U1") (pin "44") (pinfunction "VREG_44") (pintype "passive"))
    )
    (net (code "48") (name "VCC_5V") (class "Default")
      (node (ref "C11") (pin "2") (pinfunction "2_2") (pintype "passive"))
      (node (ref "C15") (pin "2") (pinfunction "2_2") (pintype "passive"))
      (node (ref "C3") (pin "2") (pinfunction "2_2") (pintype "passive"))
      (node (ref "C7") (pin "2") (pinfunction "2_2") (pintype "passive"))
      (node (ref "R27") (pin "2") (pinfunction "2_2") (pintype "passive"))
      (node (ref "U1") (pin "23") (pinfunction "EN2_23") (pintype "passive"))
      (node (ref "U1") (pin "24") (pinfunction "PVIN2_24") (pintype "passive"))
      (node (ref "U1") (pin "25") (pinfunction "PVIN2_25") (pintype "passive"))
      (node (ref "U1") (pin "35") (pinfunction "PVIN1_35") (pintype "passive"))
      (node (ref "U1") (pin "36") (pinfunction "PVIN1_36") (pintype "passive"))
      (node (ref "U1") (pin "4") (pinfunction "PVIN3_4") (pintype "passive"))
      (node (ref "U1") (pin "9") (pinfunction "PVIN4_9") (pintype "passive"))
    )
  )
)
